# eos450d.net
KiCad netlist of a schematic drawn in EAGLE
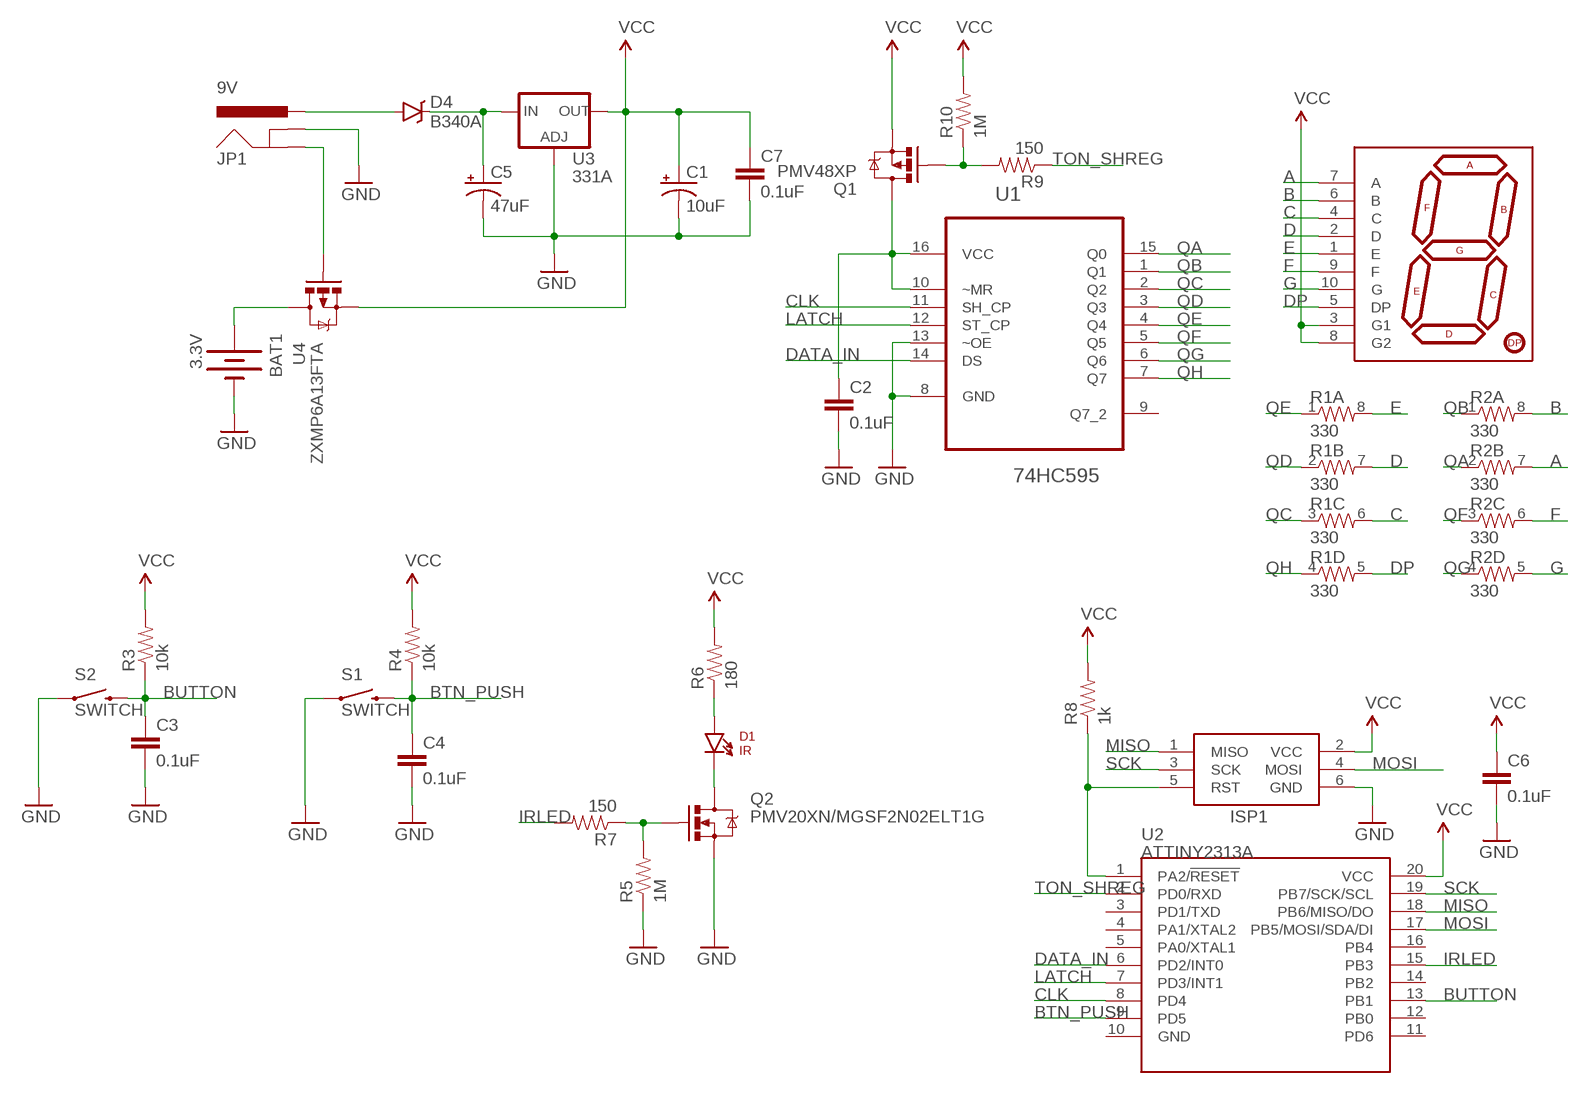
[diagram p0: schematic, sheet 1]

(export (version "E")
  (design (tool "Eeschema 10.0.6"))
  (components
    (comp (ref "BAT1")
      (value "3.3V")
      (footprint "eagle-import:BATTCOM_20MM_PTH")
      (libsource (lib "eagle-import") (part "BATTERY20PTH"))
    )
    (comp (ref "C1")
      (value "10uF")
      (footprint "eagle-import:EIA3216")
      (libsource (lib "eagle-import") (part "10UF-16V-10%(TANT)"))
    )
    (comp (ref "C2")
      (value "0.1uF")
      (footprint "eagle-import:0603-CAP")
      (libsource (lib "eagle-import") (part "0.1UF-25V-5%(0603)"))
    )
    (comp (ref "C3")
      (value "0.1uF")
      (footprint "eagle-import:0603-CAP")
      (libsource (lib "eagle-import") (part "0.1UF-25V-5%(0603)"))
    )
    (comp (ref "C4")
      (value "0.1uF")
      (footprint "eagle-import:0603-CAP")
      (libsource (lib "eagle-import") (part "0.1UF-25V-5%(0603)"))
    )
    (comp (ref "C5")
      (value "47uF")
      (footprint "eagle-import:EIA3528")
      (libsource (lib "eagle-import") (part "10UF-20V-10%(TANT)"))
    )
    (comp (ref "C6")
      (value "0.1uF")
      (footprint "eagle-import:0603-CAP")
      (libsource (lib "eagle-import") (part "0.1UF-25V-5%(0603)"))
    )
    (comp (ref "C7")
      (value "0.1uF")
      (footprint "eagle-import:0603-CAP")
      (libsource (lib "eagle-import") (part "0.1UF-25V-5%(0603)"))
    )
    (comp (ref "D1")
      (value "IR")
      (footprint "eagle-import:LTE-302")
      (libsource (lib "eagle-import") (part "LTE-302"))
    )
    (comp (ref "D2")
      (value "7-SEGMENT-DISPLAY-1\"-REDEZ")
      (footprint "eagle-import:7-SEGMENT-1_PTH-EZ")
      (libsource (lib "eagle-import") (part "7-SEGMENT-DISPLAY-1{dblquote}-REDEZ"))
    )
    (comp (ref "D4")
      (value "B340A")
      (footprint "eagle-import:SMA-DIODE")
      (libsource (lib "eagle-import") (part "DIODE-SCHOTTKY-B340A"))
    )
    (comp (ref "ISP1")
      (value "AVRISP-6")
      (footprint "eagle-import:AVRISP")
      (libsource (lib "eagle-import") (part "AVRISP-6"))
    )
    (comp (ref "JP1")
      (value "9V")
      (footprint "eagle-import:POWER_JACK_SLOT")
      (libsource (lib "eagle-import") (part "POWER_JACKSLT"))
    )
    (comp (ref "Q1")
      (value "PMV48XP")
      (footprint "eagle-import:SOT23-3")
      (libsource (lib "eagle-import") (part "PMV48XP"))
    )
    (comp (ref "Q2")
      (value "PMV20XN/MGSF2N02ELT1G")
      (footprint "eagle-import:SOT23-3")
      (libsource (lib "eagle-import") (part "PMV20XN"))
    )
    (comp (ref "R1")
      (value "330")
      (footprint "eagle-import:0603-ARV")
      (libsource (lib "eagle-import") (part "RESISTOR-ARRAY0603-ARV"))
    )
    (comp (ref "R2")
      (value "330")
      (footprint "eagle-import:0603-ARV")
      (libsource (lib "eagle-import") (part "RESISTOR-ARRAY0603-ARV"))
    )
    (comp (ref "R3")
      (value "10k")
      (footprint "eagle-import:0805")
      (libsource (lib "eagle-import") (part "RESISTOR0805-RES"))
    )
    (comp (ref "R4")
      (value "10k")
      (footprint "eagle-import:0805")
      (libsource (lib "eagle-import") (part "RESISTOR0805-RES"))
    )
    (comp (ref "R5")
      (value "1M")
      (footprint "eagle-import:0805")
      (libsource (lib "eagle-import") (part "RESISTOR0805-RES"))
    )
    (comp (ref "R6")
      (value "180")
      (footprint "eagle-import:0805")
      (libsource (lib "eagle-import") (part "RESISTOR0805-RES"))
    )
    (comp (ref "R7")
      (value "150")
      (footprint "eagle-import:0805")
      (libsource (lib "eagle-import") (part "RESISTOR0805-RES"))
    )
    (comp (ref "R8")
      (value "1k")
      (footprint "eagle-import:0805")
      (libsource (lib "eagle-import") (part "RESISTOR0805-RES"))
    )
    (comp (ref "R9")
      (value "150")
      (footprint "eagle-import:0805")
      (libsource (lib "eagle-import") (part "RESISTOR0805-RES"))
    )
    (comp (ref "R10")
      (value "1M")
      (footprint "eagle-import:0805")
      (libsource (lib "eagle-import") (part "RESISTOR0805-RES"))
    )
    (comp (ref "S1")
      (value "SWITCH")
      (footprint "eagle-import:TACTILE-PTH-EZ")
      (libsource (lib "eagle-import") (part "SWITCH-MOMENTARY-2PTH_EZ"))
    )
    (comp (ref "S2")
      (value "SWITCH")
      (footprint "eagle-import:TACTILE-PTH-EZ")
      (libsource (lib "eagle-import") (part "SWITCH-MOMENTARY-2PTH_EZ"))
    )
    (comp (ref "U1")
      (value "74HC595")
      (footprint "eagle-import:SOIC127P600X175-16N")
      (fields (field (name "MPN") "74HC595D"))
      (libsource (lib "eagle-import") (part "74HC595D"))
    )
    (comp (ref "U2")
      (value "ATTINY2313A")
      (footprint "eagle-import:SOP20W")
      (libsource (lib "eagle-import") (part "ATTINY2313A"))
    )
    (comp (ref "U3")
      (value "331A")
      (footprint "eagle-import:SOT223")
      (libsource (lib "eagle-import") (part "V_REG_317SMD"))
    )
    (comp (ref "U4")
      (value "ZXMP6A13FTA")
      (footprint "eagle-import:SOT23-3")
      (libsource (lib "eagle-import") (part "ZXMP6A13FTA"))
    )
  )
  (nets
    (net (code "1") (name "/A") (class "Default")
      (node (ref "D2") (pin "7") (pinfunction "A_7") (pintype "bidirectional"))
      (node (ref "R2") (pin "7") (pinfunction "2_7") (pintype "passive"))
    )
    (net (code "2") (name "/B") (class "Default")
      (node (ref "D2") (pin "6") (pinfunction "B_6") (pintype "bidirectional"))
      (node (ref "R2") (pin "8") (pinfunction "2_8") (pintype "passive"))
    )
    (net (code "3") (name "/BTN_PUSH") (class "Default")
      (node (ref "C4") (pin "1") (pinfunction "1_1") (pintype "passive"))
      (node (ref "R4") (pin "1") (pinfunction "1_1") (pintype "passive"))
      (node (ref "S1") (pin "3") (pinfunction "2_3") (pintype "passive"))
      (node (ref "U2") (pin "9") (pinfunction "PD5_9") (pintype "bidirectional"))
    )
    (net (code "4") (name "/BUTTON") (class "Default")
      (node (ref "C3") (pin "1") (pinfunction "1_1") (pintype "passive"))
      (node (ref "R3") (pin "1") (pinfunction "1_1") (pintype "passive"))
      (node (ref "S2") (pin "3") (pinfunction "2_3") (pintype "passive"))
      (node (ref "U2") (pin "13") (pinfunction "PB1_13") (pintype "bidirectional"))
    )
    (net (code "5") (name "/C") (class "Default")
      (node (ref "D2") (pin "4") (pinfunction "C_4") (pintype "bidirectional"))
      (node (ref "R1") (pin "6") (pinfunction "2_6") (pintype "passive"))
    )
    (net (code "6") (name "/CLK") (class "Default")
      (node (ref "U1") (pin "11") (pinfunction "SH_CP_11") (pintype "passive"))
      (node (ref "U2") (pin "8") (pinfunction "PD4_8") (pintype "bidirectional"))
    )
    (net (code "7") (name "/D") (class "Default")
      (node (ref "D2") (pin "2") (pinfunction "D_2") (pintype "bidirectional"))
      (node (ref "R1") (pin "7") (pinfunction "2_7") (pintype "passive"))
    )
    (net (code "8") (name "/DATA_IN") (class "Default")
      (node (ref "U1") (pin "14") (pinfunction "DS_14") (pintype "input"))
      (node (ref "U2") (pin "6") (pinfunction "PD2/INT0_6") (pintype "bidirectional"))
    )
    (net (code "9") (name "/DP") (class "Default")
      (node (ref "D2") (pin "5") (pinfunction "DP_5") (pintype "bidirectional"))
      (node (ref "R1") (pin "5") (pinfunction "2_5") (pintype "passive"))
    )
    (net (code "10") (name "/E") (class "Default")
      (node (ref "D2") (pin "1") (pinfunction "E_1") (pintype "bidirectional"))
      (node (ref "R1") (pin "8") (pinfunction "2_8") (pintype "passive"))
    )
    (net (code "11") (name "/F") (class "Default")
      (node (ref "D2") (pin "9") (pinfunction "F_9") (pintype "bidirectional"))
      (node (ref "R2") (pin "6") (pinfunction "2_6") (pintype "passive"))
    )
    (net (code "12") (name "/G") (class "Default")
      (node (ref "D2") (pin "10") (pinfunction "G_10") (pintype "bidirectional"))
      (node (ref "R2") (pin "5") (pinfunction "2_5") (pintype "passive"))
    )
    (net (code "13") (name "/IRLED") (class "Default")
      (node (ref "R7") (pin "2") (pinfunction "2_2") (pintype "passive"))
      (node (ref "U2") (pin "15") (pinfunction "PB3_15") (pintype "bidirectional"))
    )
    (net (code "14") (name "/LATCH") (class "Default")
      (node (ref "U1") (pin "12") (pinfunction "ST_CP_12") (pintype "passive"))
      (node (ref "U2") (pin "7") (pinfunction "PD3/INT1_7") (pintype "bidirectional"))
    )
    (net (code "15") (name "/MISO") (class "Default")
      (node (ref "ISP1") (pin "1") (pinfunction "MISO_1") (pintype "input"))
      (node (ref "U2") (pin "18") (pinfunction "PB6/MISO/DO_18") (pintype "bidirectional"))
    )
    (net (code "16") (name "/MOSI") (class "Default")
      (node (ref "ISP1") (pin "4") (pinfunction "MOSI_4") (pintype "output"))
      (node (ref "U2") (pin "17") (pinfunction "PB5/MOSI/SDA/DI_17") (pintype "bidirectional"))
    )
    (net (code "17") (name "/QA") (class "Default")
      (node (ref "R2") (pin "2") (pinfunction "1_2") (pintype "passive"))
      (node (ref "U1") (pin "15") (pinfunction "Q0_15") (pintype "output"))
    )
    (net (code "18") (name "/QB") (class "Default")
      (node (ref "R2") (pin "1") (pinfunction "1_1") (pintype "passive"))
      (node (ref "U1") (pin "1") (pinfunction "Q1_1") (pintype "output"))
    )
    (net (code "19") (name "/QC") (class "Default")
      (node (ref "R1") (pin "3") (pinfunction "1_3") (pintype "passive"))
      (node (ref "U1") (pin "2") (pinfunction "Q2_2") (pintype "output"))
    )
    (net (code "20") (name "/QD") (class "Default")
      (node (ref "R1") (pin "2") (pinfunction "1_2") (pintype "passive"))
      (node (ref "U1") (pin "3") (pinfunction "Q3_3") (pintype "output"))
    )
    (net (code "21") (name "/QE") (class "Default")
      (node (ref "R1") (pin "1") (pinfunction "1_1") (pintype "passive"))
      (node (ref "U1") (pin "4") (pinfunction "Q4_4") (pintype "output"))
    )
    (net (code "22") (name "/QF") (class "Default")
      (node (ref "R2") (pin "3") (pinfunction "1_3") (pintype "passive"))
      (node (ref "U1") (pin "5") (pinfunction "Q5_5") (pintype "output"))
    )
    (net (code "23") (name "/QG") (class "Default")
      (node (ref "R2") (pin "4") (pinfunction "1_4") (pintype "passive"))
      (node (ref "U1") (pin "6") (pinfunction "Q6_6") (pintype "output"))
    )
    (net (code "24") (name "/QH") (class "Default")
      (node (ref "R1") (pin "4") (pinfunction "1_4") (pintype "passive"))
      (node (ref "U1") (pin "7") (pinfunction "Q7_7") (pintype "output"))
    )
    (net (code "25") (name "/SCK") (class "Default")
      (node (ref "ISP1") (pin "3") (pinfunction "SCK_3") (pintype "output"))
      (node (ref "U2") (pin "19") (pinfunction "PB7/SCK/SCL_19") (pintype "bidirectional"))
    )
    (net (code "26") (name "/TON_SHREG") (class "Default")
      (node (ref "R9") (pin "1") (pinfunction "1_1") (pintype "passive"))
      (node (ref "U2") (pin "2") (pinfunction "PD0/RXD_2") (pintype "bidirectional"))
    )
    (net (code "27") (name "GND") (class "Default")
      (node (ref "BAT1") (pin "2") (pinfunction "-_2") (pintype "power_in"))
      (node (ref "C1") (pin "C") (pinfunction "-_C") (pintype "passive"))
      (node (ref "C2") (pin "2") (pinfunction "2_2") (pintype "passive"))
      (node (ref "C3") (pin "2") (pinfunction "2_2") (pintype "passive"))
      (node (ref "C4") (pin "2") (pinfunction "2_2") (pintype "passive"))
      (node (ref "C5") (pin "C") (pinfunction "-_C") (pintype "passive"))
      (node (ref "C6") (pin "2") (pinfunction "2_2") (pintype "passive"))
      (node (ref "C7") (pin "2") (pinfunction "2_2") (pintype "passive"))
      (node (ref "ISP1") (pin "6") (pinfunction "GND_6") (pintype "power_in"))
      (node (ref "JP1") (pin "GND@1") (pinfunction "GNDBREAK_GND@1") (pintype "bidirectional"))
      (node (ref "Q2") (pin "2") (pinfunction "S_2") (pintype "passive"))
      (node (ref "R5") (pin "1") (pinfunction "1_1") (pintype "passive"))
      (node (ref "S1") (pin "1") (pinfunction "1_1") (pintype "passive"))
      (node (ref "S2") (pin "1") (pinfunction "1_1") (pintype "passive"))
      (node (ref "U1") (pin "13") (pinfunction "~{OE}_13") (pintype "input"))
      (node (ref "U1") (pin "8") (pinfunction "GND_8") (pintype "passive"))
      (node (ref "U3") (pin "1") (pinfunction "ADJ_1") (pintype "input"))
    )
    (net (code "28") (name "Net-(BAT1-+)") (class "Default")
      (node (ref "BAT1") (pin "1") (pinfunction "+_1") (pintype "power_in"))
      (node (ref "U4") (pin "3") (pinfunction "D_3") (pintype "passive"))
    )
    (net (code "29") (name "Net-(C5-+)") (class "Default")
      (node (ref "C5") (pin "A") (pinfunction "+_A") (pintype "passive"))
      (node (ref "D4") (pin "C") (pinfunction "C_C") (pintype "passive"))
      (node (ref "U3") (pin "3") (pinfunction "IN_3") (pintype "input"))
    )
    (net (code "30") (name "Net-(D1-PadA)") (class "Default")
      (node (ref "D1") (pin "A") (pinfunction "A_A") (pintype "bidirectional"))
      (node (ref "R6") (pin "1") (pinfunction "1_1") (pintype "passive"))
    )
    (net (code "31") (name "Net-(D4-PadA)") (class "Default")
      (node (ref "D4") (pin "A") (pinfunction "A_A") (pintype "passive"))
      (node (ref "JP1") (pin "PWR") (pinfunction "PWR_PWR") (pintype "bidirectional"))
    )
    (net (code "32") (name "Net-(ISP1-RST)") (class "Default")
      (node (ref "ISP1") (pin "5") (pinfunction "RST_5") (pintype "output"))
      (node (ref "R8") (pin "1") (pinfunction "1_1") (pintype "passive"))
      (node (ref "U2") (pin "1") (pinfunction "PA2/~{RESET}_1") (pintype "bidirectional"))
    )
    (net (code "33") (name "Net-(JP1-GND)") (class "Default")
      (node (ref "JP1") (pin "GND@2") (pinfunction "GND_GND@2") (pintype "bidirectional"))
      (node (ref "U4") (pin "1") (pinfunction "G_1") (pintype "passive"))
    )
    (net (code "34") (name "Net-(Q1-D)") (class "Default")
      (node (ref "C2") (pin "1") (pinfunction "1_1") (pintype "passive"))
      (node (ref "Q1") (pin "3") (pinfunction "D_3") (pintype "passive"))
      (node (ref "U1") (pin "10") (pinfunction "~{MR}_10") (pintype "passive"))
      (node (ref "U1") (pin "16") (pinfunction "VCC_16") (pintype "power_in"))
    )
    (net (code "35") (name "Net-(Q1-G)") (class "Default")
      (node (ref "Q1") (pin "1") (pinfunction "G_1") (pintype "passive"))
      (node (ref "R10") (pin "1") (pinfunction "1_1") (pintype "passive"))
      (node (ref "R9") (pin "2") (pinfunction "2_2") (pintype "passive"))
    )
    (net (code "36") (name "Net-(Q2-D)") (class "Default")
      (node (ref "D1") (pin "C") (pinfunction "C_C") (pintype "bidirectional"))
      (node (ref "Q2") (pin "3") (pinfunction "D_3") (pintype "passive"))
    )
    (net (code "37") (name "Net-(Q2-G)") (class "Default")
      (node (ref "Q2") (pin "1") (pinfunction "G_1") (pintype "passive"))
      (node (ref "R5") (pin "2") (pinfunction "2_2") (pintype "passive"))
      (node (ref "R7") (pin "1") (pinfunction "1_1") (pintype "passive"))
    )
    (net (code "38") (name "VCC") (class "Default")
      (node (ref "C1") (pin "A") (pinfunction "+_A") (pintype "passive"))
      (node (ref "C6") (pin "1") (pinfunction "1_1") (pintype "passive"))
      (node (ref "C7") (pin "1") (pinfunction "1_1") (pintype "passive"))
      (node (ref "D2") (pin "3") (pinfunction "G1_3") (pintype "bidirectional"))
      (node (ref "D2") (pin "8") (pinfunction "G2_8") (pintype "bidirectional"))
      (node (ref "ISP1") (pin "2") (pinfunction "VCC_2") (pintype "power_in"))
      (node (ref "Q1") (pin "2") (pinfunction "S_2") (pintype "passive"))
      (node (ref "R10") (pin "2") (pinfunction "2_2") (pintype "passive"))
      (node (ref "R3") (pin "2") (pinfunction "2_2") (pintype "passive"))
      (node (ref "R4") (pin "2") (pinfunction "2_2") (pintype "passive"))
      (node (ref "R6") (pin "2") (pinfunction "2_2") (pintype "passive"))
      (node (ref "R8") (pin "2") (pinfunction "2_2") (pintype "passive"))
      (node (ref "U2") (pin "20") (pinfunction "VCC_20") (pintype "bidirectional"))
      (node (ref "U3") (pin "2") (pinfunction "OUT_2") (pintype "output"))
      (node (ref "U4") (pin "2") (pinfunction "S_2") (pintype "passive"))
    )
    (net (code "39") (name "unconnected-(U1-Q7_2-Pad9)") (class "Default")
      (node (ref "U1") (pin "9") (pinfunction "Q7_2_9") (pintype "output"))
    )
    (net (code "40") (name "unconnected-(U2-GND-Pad10)") (class "Default")
      (node (ref "U2") (pin "10") (pinfunction "GND_10") (pintype "bidirectional"))
    )
    (net (code "41") (name "unconnected-(U2-PA0{slash}XTAL1-Pad5)") (class "Default")
      (node (ref "U2") (pin "5") (pinfunction "PA0/XTAL1_5") (pintype "bidirectional"))
    )
    (net (code "42") (name "unconnected-(U2-PA1{slash}XTAL2-Pad4)") (class "Default")
      (node (ref "U2") (pin "4") (pinfunction "PA1/XTAL2_4") (pintype "bidirectional"))
    )
    (net (code "43") (name "unconnected-(U2-PB0-Pad12)") (class "Default")
      (node (ref "U2") (pin "12") (pinfunction "PB0_12") (pintype "bidirectional"))
    )
    (net (code "44") (name "unconnected-(U2-PB2-Pad14)") (class "Default")
      (node (ref "U2") (pin "14") (pinfunction "PB2_14") (pintype "bidirectional"))
    )
    (net (code "45") (name "unconnected-(U2-PB4-Pad16)") (class "Default")
      (node (ref "U2") (pin "16") (pinfunction "PB4_16") (pintype "bidirectional"))
    )
    (net (code "46") (name "unconnected-(U2-PD1{slash}TXD-Pad3)") (class "Default")
      (node (ref "U2") (pin "3") (pinfunction "PD1/TXD_3") (pintype "bidirectional"))
    )
    (net (code "47") (name "unconnected-(U2-PD6-Pad11)") (class "Default")
      (node (ref "U2") (pin "11") (pinfunction "PD6_11") (pintype "bidirectional"))
    )
  )
)
